# Alimentacion.net
KiCad netlist of a schematic drawn in Altium Designer
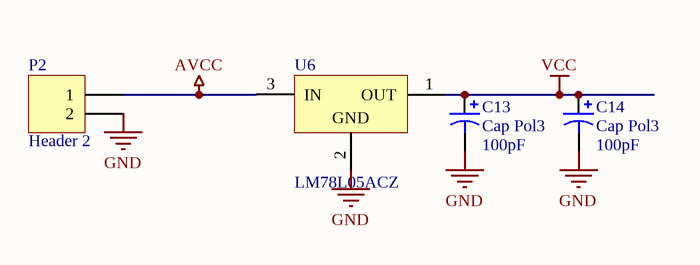
[diagram p0: Alimentacion.SchDoc]

(export (version "E")
  (design (tool "Eeschema 10.0.6"))
  (components
    (comp (ref "C13")
      (value "Cap Pol3")
      (footprint "C0805")
      (description "Polarized Capacitor (Surface Mount)")
      (fields (field (name "ALTIUM_VALUE") "100pF") (field (name "PUBLISHER") "Altium Limited"))
      (libsource (lib "Miscellaneous Devices") (part "Cap Pol3"))
    )
    (comp (ref "C14")
      (value "Cap Pol3")
      (footprint "C0805")
      (description "Polarized Capacitor (Surface Mount)")
      (fields (field (name "ALTIUM_VALUE") "100pF") (field (name "PUBLISHER") "Altium Limited"))
      (libsource (lib "Miscellaneous Devices") (part "Cap Pol3"))
    )
    (comp (ref "P2")
      (value "Header 2")
      (footprint "HDR1X2")
      (description "Header, 2-Pin")
      (fields (field (name "PUBLISHER") "Altium Limited"))
      (libsource (lib "Miscellaneous Connectors") (part "Header 2"))
    )
    (comp (ref "U6")
      (value "LM78L05ACZ")
      (footprint "Z03A")
      (description "3-Terminal Positive Regulators")
      (fields
        (field (name "MANUFACTURER") "National Semiconductor")
        (field (name "DIGIKEYPARTNUMBER") "LM78L05ACZNS-ND")
        (field (name "PUBLISHER") "Altium Limited")
      )
      (libsource (lib "NSC LDO") (part "LM78L05ACZ"))
    )
  )
  (nets
    (net (code "1") (name "AVCC") (class "Default")
      (node (ref "P2") (pin "1") (pinfunction "1_1") (pintype "passive"))
      (node (ref "U6") (pin "3") (pinfunction "IN_3") (pintype "power_in"))
    )
    (net (code "2") (name "GND") (class "Default")
      (node (ref "C13") (pin "2") (pinfunction "2_2") (pintype "passive"))
      (node (ref "C14") (pin "2") (pinfunction "2_2") (pintype "passive"))
      (node (ref "P2") (pin "2") (pinfunction "2_2") (pintype "passive"))
      (node (ref "U6") (pin "2") (pinfunction "GND_2") (pintype "power_in"))
    )
    (net (code "3") (name "VCC") (class "Default")
      (node (ref "C13") (pin "1") (pinfunction "1_1") (pintype "passive"))
      (node (ref "C14") (pin "1") (pinfunction "1_1") (pintype "passive"))
      (node (ref "U6") (pin "1") (pinfunction "OUT_1") (pintype "power_in"))
    )
  )
)
